# FPGA_B34_B35.net
KiCad netlist of a schematic drawn in Altium Designer
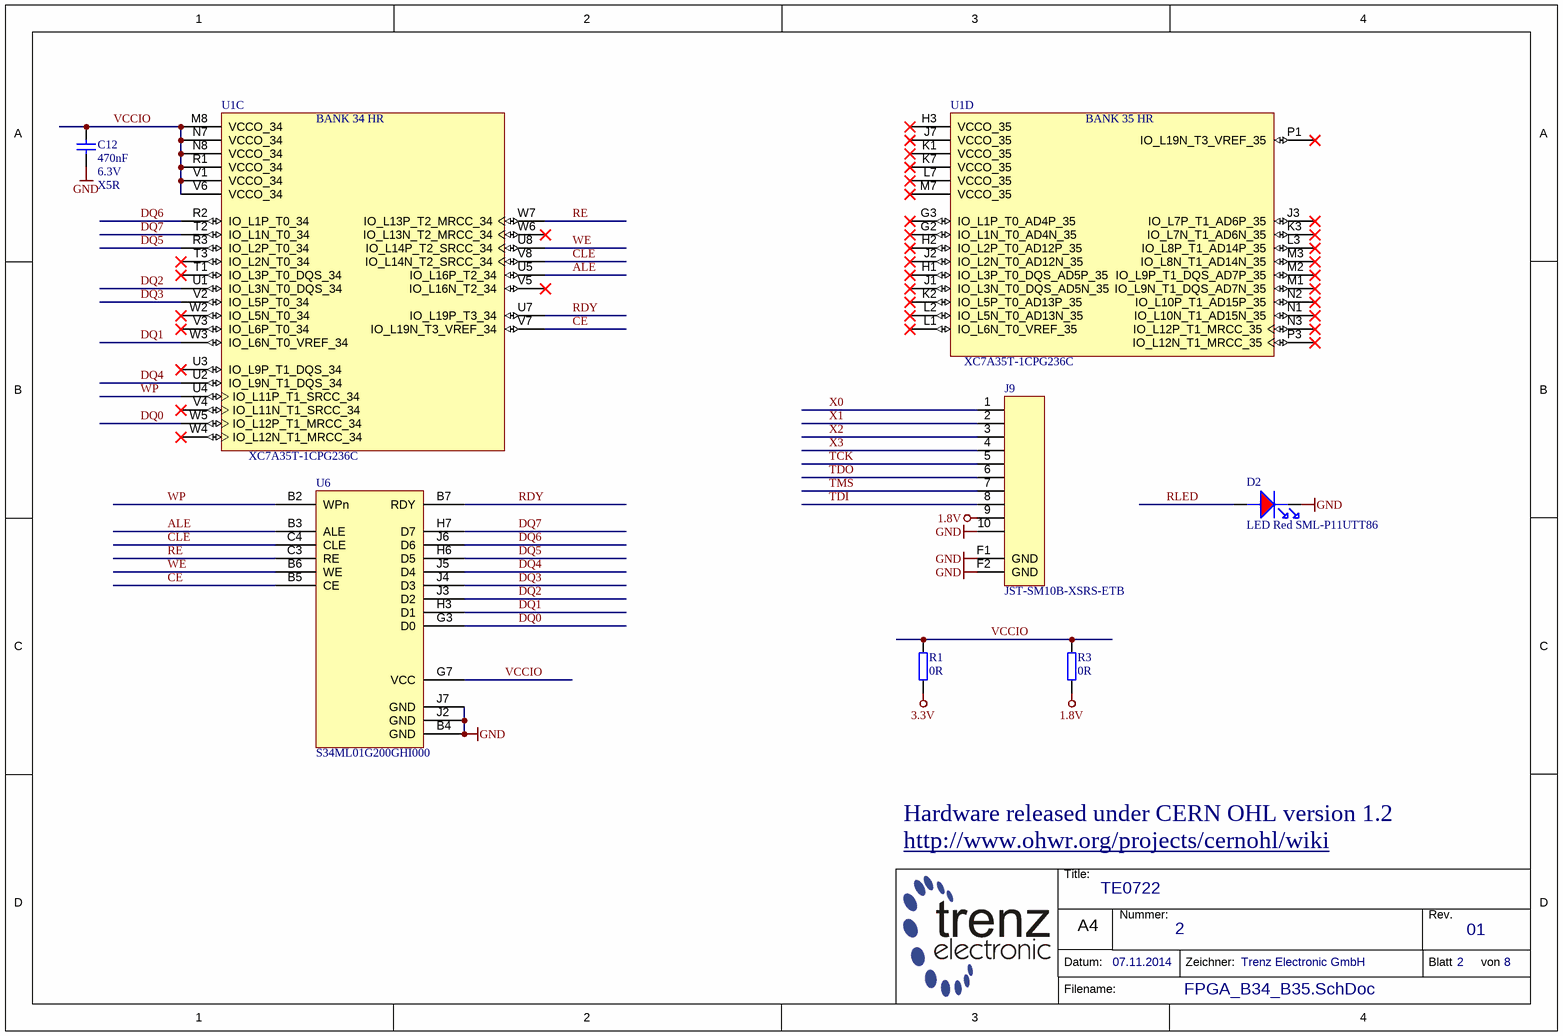
[diagram p0: FPGA_B34_B35.SchDoc]

(export (version "E")
  (design (tool "Eeschema 10.0.6"))
  (components
    (comp (ref "C12")
      (value "470nF")
      (footprint "CAPC0603X33N")
      (description "KON 470nF X5R 6.3V SMD 20%")
      (fields
        (field (name "VOLTAGE") "6.3V")
        (field (name "TECHNOLOGY") "X5R")
        (field (name "TOLERANCE") "20%")
      )
      (libsource (lib "TE") (part "CAP-NP"))
    )
    (comp (ref "D2")
      (value "LED Red SML-P11UTT86")
      (footprint "LEDC1006X25N_RED")
      (description "LED Rot SML-P11UTT86 SMD")
      (libsource (lib "TE") (part "LED_ROT"))
    )
    (comp (ref "J9")
      (value "JST-SM10B-XSRS-ETB")
      (footprint "JST-SM10B-XSRS-ETB")
      (description "JST 10Pol. 0.6mm RA")
      (libsource (lib "TE") (part "SM10B-XSRS-ETB"))
    )
    (comp (ref "R1")
      (value "0R")
      (footprint "RESC0603X26N")
      (description "WID SMD 0R 0,05W SMD")
      (libsource (lib "TE") (part "RES"))
    )
    (comp (ref "R3")
      (value "0R")
      (footprint "RESC0603X26N")
      (description "WID SMD 0R 0,05W SMD")
      (libsource (lib "TE") (part "RES"))
    )
    (comp (ref "U1")
      (value "XC7A35T-1CPG236C")
      (footprint "XC7AxxT-CPG236")
      (libsource (lib "TE") (part "XC7A35T-CPG236"))
    )
    (comp (ref "U6")
      (value "S34ML01G200GHI000")
      (footprint "BGA67C80P10X8_800X650X100B46N")
      (libsource (lib "TE") (part "S34ML0xG2-BGA67"))
    )
  )
  (nets
    (net (code "1") (name "/ALE") (class "Default")
      (node (ref "U1") (pin "U5") (pinfunction "IO_L16P_T2_34_U5") (pintype "bidirectional"))
      (node (ref "U6") (pin "B3") (pinfunction "ALE_B3") (pintype "passive"))
    )
    (net (code "2") (name "/CE") (class "Default")
      (node (ref "U1") (pin "V7") (pinfunction "IO_L19N_T3_VREF_34_V7") (pintype "bidirectional"))
      (node (ref "U6") (pin "B5") (pinfunction "CE_B5") (pintype "passive"))
    )
    (net (code "3") (name "/CLE") (class "Default")
      (node (ref "U1") (pin "V8") (pinfunction "IO_L14N_T2_SRCC_34_V8") (pintype "bidirectional"))
      (node (ref "U6") (pin "C4") (pinfunction "CLE_C4") (pintype "passive"))
    )
    (net (code "4") (name "/DQ0") (class "Default")
      (node (ref "U1") (pin "W5") (pinfunction "IO_L12P_T1_MRCC_34_W5") (pintype "bidirectional"))
      (node (ref "U6") (pin "G3") (pinfunction "D0_G3") (pintype "passive"))
    )
    (net (code "5") (name "/DQ1") (class "Default")
      (node (ref "U1") (pin "W3") (pinfunction "IO_L6N_T0_VREF_34_W3") (pintype "bidirectional"))
      (node (ref "U6") (pin "H3") (pinfunction "D1_H3") (pintype "passive"))
    )
    (net (code "6") (name "/DQ2") (class "Default")
      (node (ref "U1") (pin "U1") (pinfunction "IO_L3N_T0_DQS_34_U1") (pintype "bidirectional"))
      (node (ref "U6") (pin "J3") (pinfunction "D2_J3") (pintype "passive"))
    )
    (net (code "7") (name "/DQ3") (class "Default")
      (node (ref "U1") (pin "V2") (pinfunction "IO_L5P_T0_34_V2") (pintype "bidirectional"))
      (node (ref "U6") (pin "J4") (pinfunction "D3_J4") (pintype "passive"))
    )
    (net (code "8") (name "/DQ4") (class "Default")
      (node (ref "U1") (pin "U2") (pinfunction "IO_L9N_T1_DQS_34_U2") (pintype "bidirectional"))
      (node (ref "U6") (pin "J5") (pinfunction "D4_J5") (pintype "passive"))
    )
    (net (code "9") (name "/DQ5") (class "Default")
      (node (ref "U1") (pin "R3") (pinfunction "IO_L2P_T0_34_R3") (pintype "bidirectional"))
      (node (ref "U6") (pin "H6") (pinfunction "D5_H6") (pintype "passive"))
    )
    (net (code "10") (name "/DQ6") (class "Default")
      (node (ref "U1") (pin "R2") (pinfunction "IO_L1P_T0_34_R2") (pintype "bidirectional"))
      (node (ref "U6") (pin "J6") (pinfunction "D6_J6") (pintype "passive"))
    )
    (net (code "11") (name "/DQ7") (class "Default")
      (node (ref "U1") (pin "T2") (pinfunction "IO_L1N_T0_34_T2") (pintype "bidirectional"))
      (node (ref "U6") (pin "H7") (pinfunction "D7_H7") (pintype "passive"))
    )
    (net (code "12") (name "/RDY") (class "Default")
      (node (ref "U1") (pin "U7") (pinfunction "IO_L19P_T3_34_U7") (pintype "bidirectional"))
      (node (ref "U6") (pin "B7") (pinfunction "RDY_B7") (pintype "passive"))
    )
    (net (code "13") (name "/RE") (class "Default")
      (node (ref "U1") (pin "W7") (pinfunction "IO_L13P_T2_MRCC_34_W7") (pintype "bidirectional"))
      (node (ref "U6") (pin "C3") (pinfunction "RE_C3") (pintype "passive"))
    )
    (net (code "14") (name "/RLED") (class "Default")
      (node (ref "D2") (pin "A") (pinfunction "A_A") (pintype "passive"))
    )
    (net (code "15") (name "/TCK") (class "Default") (node (ref "J9") (pin "5") (pintype "passive")))
    (net (code "16") (name "/TDI") (class "Default") (node (ref "J9") (pin "8") (pintype "passive")))
    (net (code "17") (name "/TDO") (class "Default") (node (ref "J9") (pin "6") (pintype "passive")))
    (net (code "18") (name "/TMS") (class "Default") (node (ref "J9") (pin "7") (pintype "passive")))
    (net (code "19") (name "/VCCIO") (class "Default")
      (node (ref "C12") (pin "1") (pinfunction "1_1") (pintype "passive"))
      (node (ref "R1") (pin "1") (pinfunction "1_1") (pintype "passive"))
      (node (ref "R3") (pin "1") (pinfunction "1_1") (pintype "passive"))
      (node (ref "U1") (pin "M8") (pinfunction "VCCO_34_M8") (pintype "power_in"))
      (node (ref "U1") (pin "N7") (pinfunction "VCCO_34_N7") (pintype "power_in"))
      (node (ref "U1") (pin "N8") (pinfunction "VCCO_34_N8") (pintype "power_in"))
      (node (ref "U1") (pin "R1") (pinfunction "VCCO_34_R1") (pintype "power_in"))
      (node (ref "U1") (pin "V1") (pinfunction "VCCO_34_V1") (pintype "power_in"))
      (node (ref "U1") (pin "V6") (pinfunction "VCCO_34_V6") (pintype "power_in"))
      (node (ref "U6") (pin "G7") (pinfunction "VCC_G7") (pintype "passive"))
    )
    (net (code "20") (name "/WE") (class "Default")
      (node (ref "U1") (pin "U8") (pinfunction "IO_L14P_T2_SRCC_34_U8") (pintype "bidirectional"))
      (node (ref "U6") (pin "B6") (pinfunction "WE_B6") (pintype "passive"))
    )
    (net (code "21") (name "/WP") (class "Default")
      (node (ref "U1") (pin "U4") (pinfunction "IO_L11P_T1_SRCC_34_U4") (pintype "bidirectional"))
      (node (ref "U6") (pin "B2") (pinfunction "WPn_B2") (pintype "passive"))
    )
    (net (code "22") (name "/X0") (class "Default") (node (ref "J9") (pin "1") (pintype "passive")))
    (net (code "23") (name "/X1") (class "Default") (node (ref "J9") (pin "2") (pintype "passive")))
    (net (code "24") (name "/X2") (class "Default") (node (ref "J9") (pin "3") (pintype "passive")))
    (net (code "25") (name "/X3") (class "Default") (node (ref "J9") (pin "4") (pintype "passive")))
    (net (code "26") (name "1.8V") (class "Default")
      (node (ref "J9") (pin "9") (pintype "passive"))
      (node (ref "R3") (pin "2") (pinfunction "2_2") (pintype "passive"))
    )
    (net (code "27") (name "3.3V") (class "Default")
      (node (ref "R1") (pin "2") (pinfunction "2_2") (pintype "passive"))
    )
    (net (code "28") (name "GND") (class "Default")
      (node (ref "C12") (pin "2") (pinfunction "2_2") (pintype "passive"))
      (node (ref "D2") (pin "K") (pinfunction "K_K") (pintype "passive"))
      (node (ref "J9") (pin "10") (pintype "passive"))
      (node (ref "J9") (pin "F1") (pinfunction "GND_F1") (pintype "passive"))
      (node (ref "J9") (pin "F2") (pinfunction "GND_F2") (pintype "passive"))
      (node (ref "U6") (pin "B4") (pinfunction "GND_B4") (pintype "passive"))
      (node (ref "U6") (pin "J2") (pinfunction "GND_J2") (pintype "passive"))
      (node (ref "U6") (pin "J7") (pinfunction "GND_J7") (pintype "passive"))
    )
    (net (code "29") (name "unconnected-(U1C-IO_L2N_T0_34-PadT3)") (class "Default")
      (node (ref "U1") (pin "T3") (pinfunction "IO_L2N_T0_34_T3") (pintype "bidirectional+no_connect"))
    )
    (net (code "30") (name "unconnected-(U1C-IO_L3P_T0_DQS_34-PadT1)") (class "Default")
      (node (ref "U1") (pin "T1") (pinfunction "IO_L3P_T0_DQS_34_T1") (pintype "bidirectional+no_connect"))
    )
    (net (code "31") (name "unconnected-(U1C-IO_L5N_T0_34-PadW2)") (class "Default")
      (node (ref "U1") (pin "W2") (pinfunction "IO_L5N_T0_34_W2") (pintype "bidirectional+no_connect"))
    )
    (net (code "32") (name "unconnected-(U1C-IO_L6P_T0_34-PadV3)") (class "Default")
      (node (ref "U1") (pin "V3") (pinfunction "IO_L6P_T0_34_V3") (pintype "bidirectional+no_connect"))
    )
    (net (code "33") (name "unconnected-(U1C-IO_L9P_T1_DQS_34-PadU3)") (class "Default")
      (node (ref "U1") (pin "U3") (pinfunction "IO_L9P_T1_DQS_34_U3") (pintype "bidirectional+no_connect"))
    )
    (net (code "34") (name "unconnected-(U1C-IO_L11N_T1_SRCC_34-PadV4)") (class "Default")
      (node (ref "U1") (pin "V4") (pinfunction "IO_L11N_T1_SRCC_34_V4") (pintype "bidirectional+no_connect"))
    )
    (net (code "35") (name "unconnected-(U1C-IO_L12N_T1_MRCC_34-PadW4)") (class "Default")
      (node (ref "U1") (pin "W4") (pinfunction "IO_L12N_T1_MRCC_34_W4") (pintype "bidirectional+no_connect"))
    )
    (net (code "36") (name "unconnected-(U1C-IO_L13N_T2_MRCC_34-PadW6)") (class "Default")
      (node (ref "U1") (pin "W6") (pinfunction "IO_L13N_T2_MRCC_34_W6") (pintype "bidirectional+no_connect"))
    )
    (net (code "37") (name "unconnected-(U1C-IO_L16N_T2_34-PadV5)") (class "Default")
      (node (ref "U1") (pin "V5") (pinfunction "IO_L16N_T2_34_V5") (pintype "bidirectional+no_connect"))
    )
    (net (code "38") (name "unconnected-(U1D-IO_L1N_T0_AD4N_35-PadG2)") (class "Default")
      (node (ref "U1") (pin "G2") (pinfunction "IO_L1N_T0_AD4N_35_G2") (pintype "bidirectional+no_connect"))
    )
    (net (code "39") (name "unconnected-(U1D-IO_L1P_T0_AD4P_35-PadG3)") (class "Default")
      (node (ref "U1") (pin "G3") (pinfunction "IO_L1P_T0_AD4P_35_G3") (pintype "bidirectional+no_connect"))
    )
    (net (code "40") (name "unconnected-(U1D-IO_L2N_T0_AD12N_35-PadJ2)") (class "Default")
      (node (ref "U1") (pin "J2") (pinfunction "IO_L2N_T0_AD12N_35_J2") (pintype "bidirectional+no_connect"))
    )
    (net (code "41") (name "unconnected-(U1D-IO_L2P_T0_AD12P_35-PadH2)") (class "Default")
      (node (ref "U1") (pin "H2") (pinfunction "IO_L2P_T0_AD12P_35_H2") (pintype "bidirectional+no_connect"))
    )
    (net (code "42") (name "unconnected-(U1D-IO_L3N_T0_DQS_AD5N_35-PadJ1)") (class "Default")
      (node (ref "U1") (pin "J1") (pinfunction "IO_L3N_T0_DQS_AD5N_35_J1") (pintype "bidirectional+no_connect"))
    )
    (net (code "43") (name "unconnected-(U1D-IO_L3P_T0_DQS_AD5P_35-PadH1)") (class "Default")
      (node (ref "U1") (pin "H1") (pinfunction "IO_L3P_T0_DQS_AD5P_35_H1") (pintype "bidirectional+no_connect"))
    )
    (net (code "44") (name "unconnected-(U1D-IO_L5N_T0_AD13N_35-PadL2)") (class "Default")
      (node (ref "U1") (pin "L2") (pinfunction "IO_L5N_T0_AD13N_35_L2") (pintype "bidirectional+no_connect"))
    )
    (net (code "45") (name "unconnected-(U1D-IO_L5P_T0_AD13P_35-PadK2)") (class "Default")
      (node (ref "U1") (pin "K2") (pinfunction "IO_L5P_T0_AD13P_35_K2") (pintype "bidirectional+no_connect"))
    )
    (net (code "46") (name "unconnected-(U1D-IO_L6N_T0_VREF_35-PadL1)") (class "Default")
      (node (ref "U1") (pin "L1") (pinfunction "IO_L6N_T0_VREF_35_L1") (pintype "bidirectional+no_connect"))
    )
    (net (code "47") (name "unconnected-(U1D-IO_L7N_T1_AD6N_35-PadK3)") (class "Default")
      (node (ref "U1") (pin "K3") (pinfunction "IO_L7N_T1_AD6N_35_K3") (pintype "bidirectional+no_connect"))
    )
    (net (code "48") (name "unconnected-(U1D-IO_L7P_T1_AD6P_35-PadJ3)") (class "Default")
      (node (ref "U1") (pin "J3") (pinfunction "IO_L7P_T1_AD6P_35_J3") (pintype "bidirectional+no_connect"))
    )
    (net (code "49") (name "unconnected-(U1D-IO_L8N_T1_AD14N_35-PadM3)") (class "Default")
      (node (ref "U1") (pin "M3") (pinfunction "IO_L8N_T1_AD14N_35_M3") (pintype "bidirectional+no_connect"))
    )
    (net (code "50") (name "unconnected-(U1D-IO_L8P_T1_AD14P_35-PadL3)") (class "Default")
      (node (ref "U1") (pin "L3") (pinfunction "IO_L8P_T1_AD14P_35_L3") (pintype "bidirectional+no_connect"))
    )
    (net (code "51") (name "unconnected-(U1D-IO_L9N_T1_DQS_AD7N_35-PadM1)") (class "Default")
      (node (ref "U1") (pin "M1") (pinfunction "IO_L9N_T1_DQS_AD7N_35_M1") (pintype "bidirectional+no_connect"))
    )
    (net (code "52") (name "unconnected-(U1D-IO_L9P_T1_DQS_AD7P_35-PadM2)") (class "Default")
      (node (ref "U1") (pin "M2") (pinfunction "IO_L9P_T1_DQS_AD7P_35_M2") (pintype "bidirectional+no_connect"))
    )
    (net (code "53") (name "unconnected-(U1D-IO_L10N_T1_AD15N_35-PadN1)") (class "Default")
      (node (ref "U1") (pin "N1") (pinfunction "IO_L10N_T1_AD15N_35_N1") (pintype "bidirectional+no_connect"))
    )
    (net (code "54") (name "unconnected-(U1D-IO_L10P_T1_AD15P_35-PadN2)") (class "Default")
      (node (ref "U1") (pin "N2") (pinfunction "IO_L10P_T1_AD15P_35_N2") (pintype "bidirectional+no_connect"))
    )
    (net (code "55") (name "unconnected-(U1D-IO_L12N_T1_MRCC_35-PadP3)") (class "Default")
      (node (ref "U1") (pin "P3") (pinfunction "IO_L12N_T1_MRCC_35_P3") (pintype "bidirectional+no_connect"))
    )
    (net (code "56") (name "unconnected-(U1D-IO_L12P_T1_MRCC_35-PadN3)") (class "Default")
      (node (ref "U1") (pin "N3") (pinfunction "IO_L12P_T1_MRCC_35_N3") (pintype "bidirectional+no_connect"))
    )
    (net (code "57") (name "unconnected-(U1D-IO_L19N_T3_VREF_35-PadP1)") (class "Default")
      (node (ref "U1") (pin "P1") (pinfunction "IO_L19N_T3_VREF_35_P1") (pintype "bidirectional+no_connect"))
    )
    (net (code "58") (name "unconnected-(U1D-VCCO_35-PadH3)") (class "Default")
      (node (ref "U1") (pin "H3") (pinfunction "VCCO_35_H3") (pintype "power_in+no_connect"))
    )
    (net (code "59") (name "unconnected-(U1D-VCCO_35-PadJ7)") (class "Default")
      (node (ref "U1") (pin "J7") (pinfunction "VCCO_35_J7") (pintype "power_in+no_connect"))
    )
    (net (code "60") (name "unconnected-(U1D-VCCO_35-PadK1)") (class "Default")
      (node (ref "U1") (pin "K1") (pinfunction "VCCO_35_K1") (pintype "power_in+no_connect"))
    )
    (net (code "61") (name "unconnected-(U1D-VCCO_35-PadK7)") (class "Default")
      (node (ref "U1") (pin "K7") (pinfunction "VCCO_35_K7") (pintype "power_in+no_connect"))
    )
    (net (code "62") (name "unconnected-(U1D-VCCO_35-PadL7)") (class "Default")
      (node (ref "U1") (pin "L7") (pinfunction "VCCO_35_L7") (pintype "power_in+no_connect"))
    )
    (net (code "63") (name "unconnected-(U1D-VCCO_35-PadM7)") (class "Default")
      (node (ref "U1") (pin "M7") (pinfunction "VCCO_35_M7") (pintype "power_in+no_connect"))
    )
  )
)
